# jtag_levelxlate.net
KiCad netlist of a schematic drawn in Altium Designer
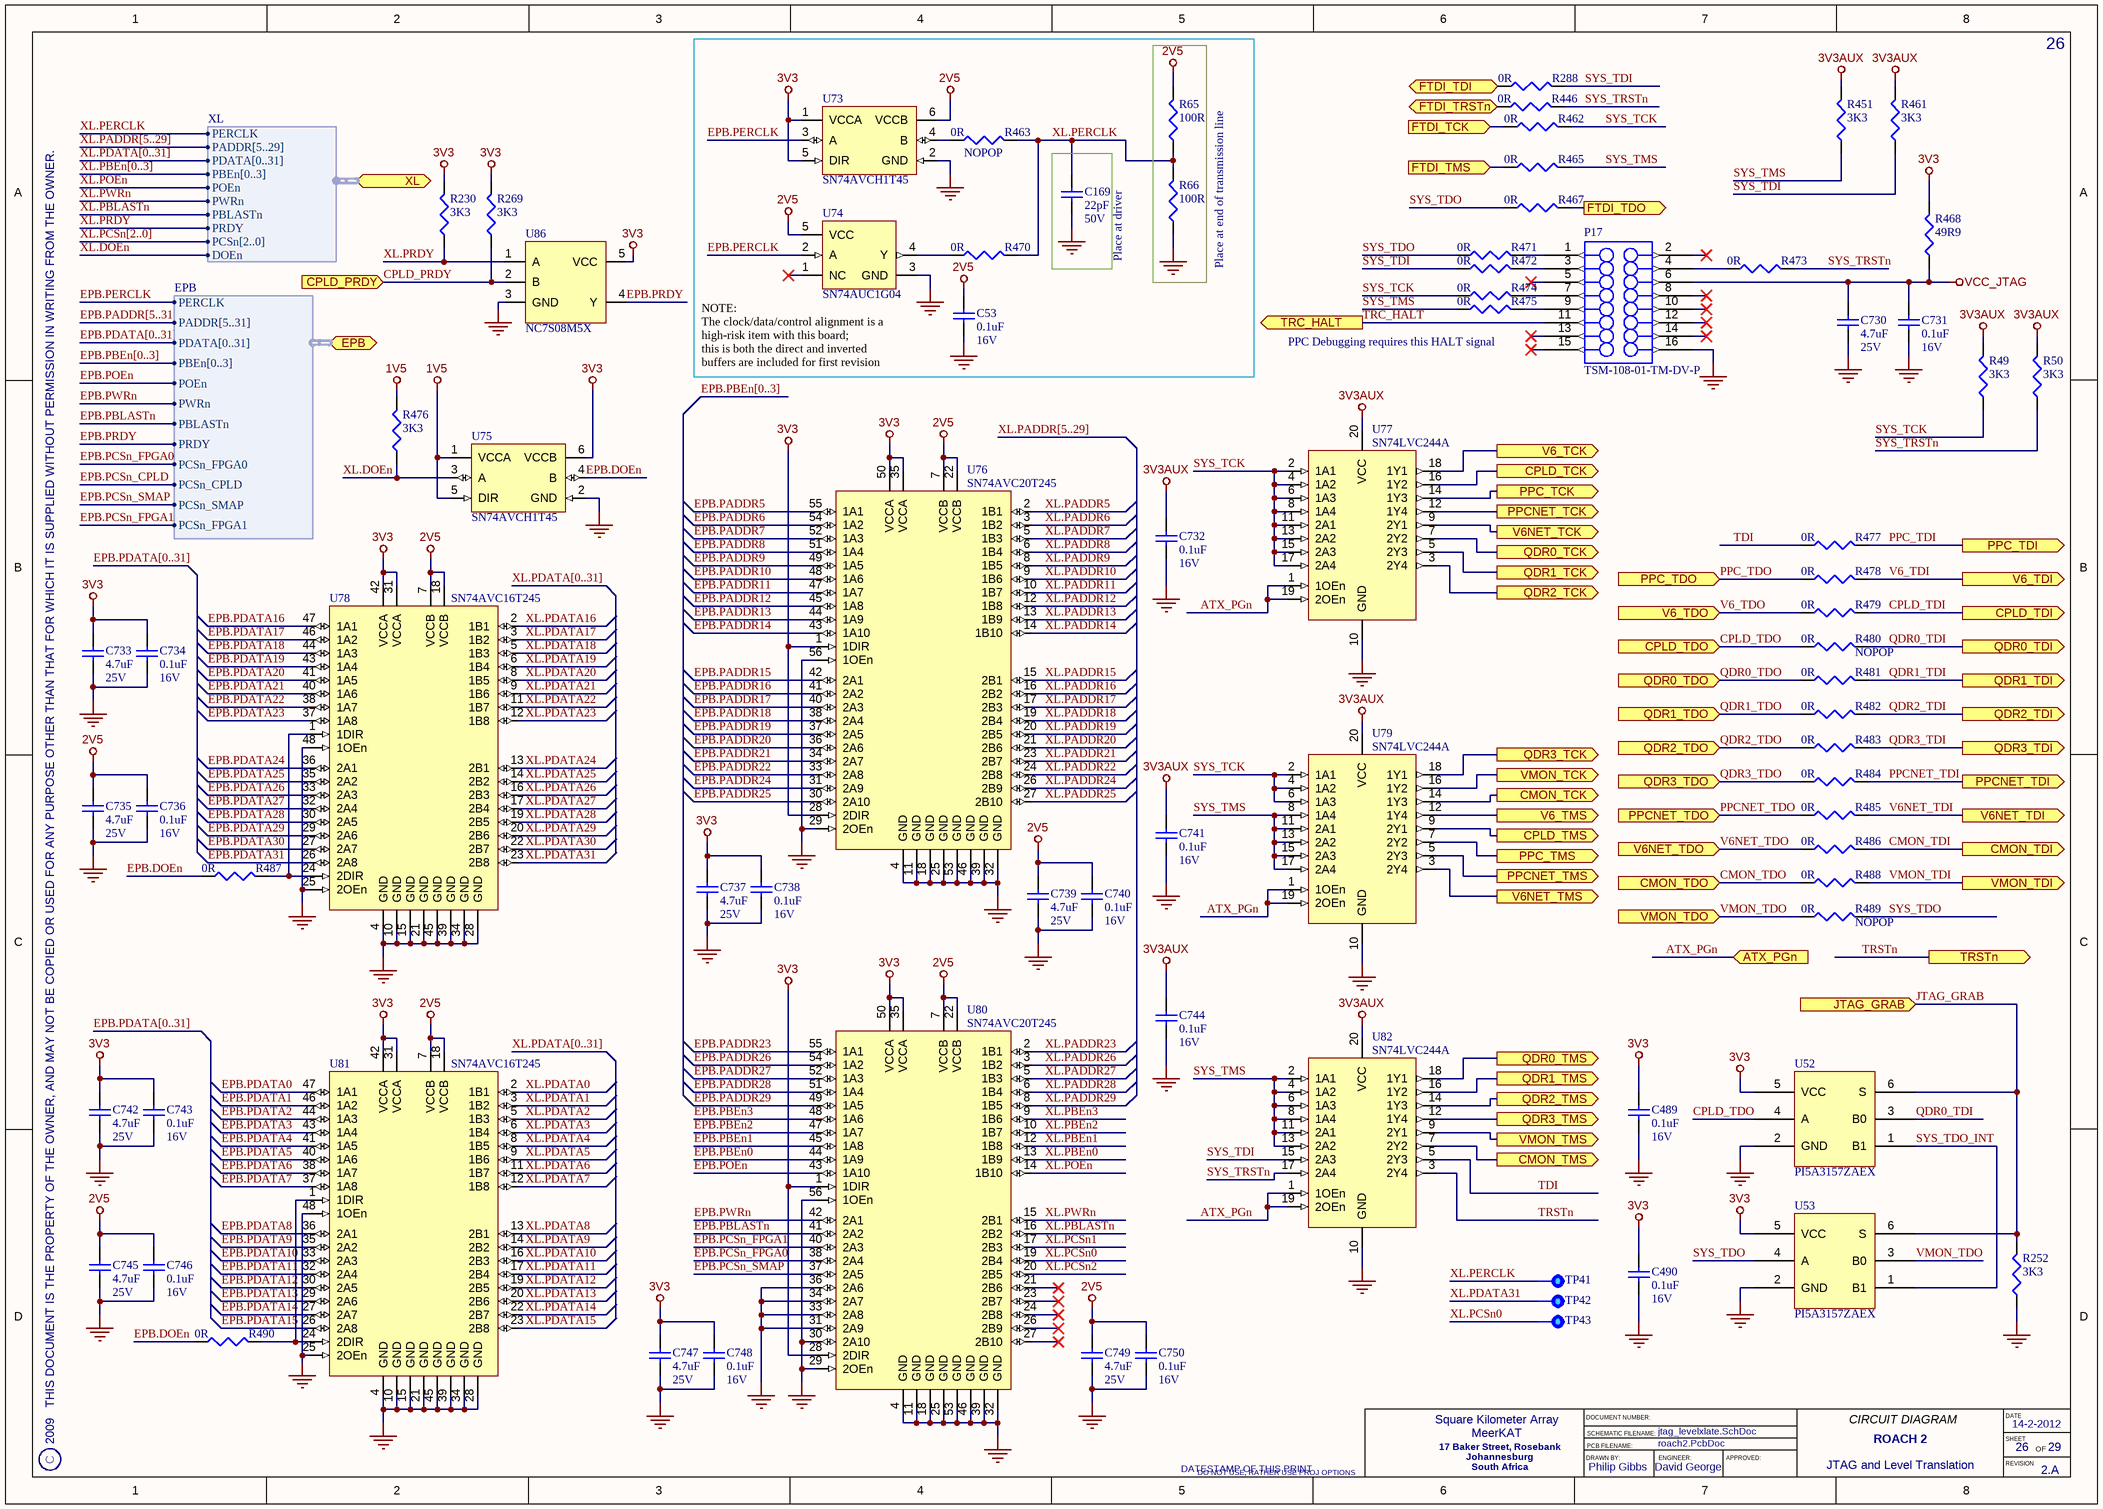
[diagram p0: jtag_levelxlate.SchDoc]

(export (version "E")
  (design (tool "Eeschema 10.0.6"))
  (components
    (comp (ref "C53")
      (value "0.1uF")
      (footprint "CAPC1005X60L")
      (description "0.1uF, Ceramic Capacitor")
      (fields
        (field (name "RATING") "16V")
        (field (name "MANUFACTURER") "VENKEL")
        (field (name "PARTNUM") "C0402X7R160-104KN")
      )
      (libsource (lib "altium_db") (part "CapStd"))
    )
    (comp (ref "C169")
      (value "22pF")
      (footprint "CAPC1005X55L")
      (description "22pF, Ceramic Capacitor")
      (fields
        (field (name "RATING") "50V")
        (field (name "MANUFACTURER") "MURATA")
        (field (name "PARTNUM") "GRM1555C1H220JZ01D")
      )
      (libsource (lib "altium_db") (part "CapStd"))
    )
    (comp (ref "C489")
      (value "0.1uF")
      (footprint "CAPC1005X60L")
      (description "0.1uF, Ceramic Capacitor")
      (fields
        (field (name "RATING") "16V")
        (field (name "MANUFACTURER") "VENKEL")
        (field (name "PARTNUM") "C0402X7R160-104KN")
      )
      (libsource (lib "altium_db") (part "CapStd"))
    )
    (comp (ref "C490")
      (value "0.1uF")
      (footprint "CAPC1005X60L")
      (description "0.1uF, Ceramic Capacitor")
      (fields
        (field (name "RATING") "16V")
        (field (name "MANUFACTURER") "VENKEL")
        (field (name "PARTNUM") "C0402X7R160-104KN")
      )
      (libsource (lib "altium_db") (part "CapStd"))
    )
    (comp (ref "C730")
      (value "4.7uF")
      (footprint "CAPC2012X127L")
      (description "4.7uF, Ceramic Capacitor")
      (fields
        (field (name "RATING") "25V")
        (field (name "MANUFACTURER") "MURATA")
        (field (name "PARTNUM") "GRM21BR61E475KA12K")
      )
      (libsource (lib "altium_db") (part "CapStd"))
    )
    (comp (ref "C731")
      (value "0.1uF")
      (footprint "CAPC1005X60L")
      (description "0.1uF, Ceramic Capacitor")
      (fields
        (field (name "RATING") "16V")
        (field (name "MANUFACTURER") "VENKEL")
        (field (name "PARTNUM") "C0402X7R160-104KN")
      )
      (libsource (lib "altium_db") (part "CapStd"))
    )
    (comp (ref "C732")
      (value "0.1uF")
      (footprint "CAPC1005X60L")
      (description "0.1uF, Ceramic Capacitor")
      (fields
        (field (name "RATING") "16V")
        (field (name "MANUFACTURER") "VENKEL")
        (field (name "PARTNUM") "C0402X7R160-104KN")
      )
      (libsource (lib "altium_db") (part "CapStd"))
    )
    (comp (ref "C733")
      (value "4.7uF")
      (footprint "CAPC2012X127L")
      (description "4.7uF, Ceramic Capacitor")
      (fields
        (field (name "RATING") "25V")
        (field (name "MANUFACTURER") "MURATA")
        (field (name "PARTNUM") "GRM21BR61E475KA12K")
      )
      (libsource (lib "altium_db") (part "CapStd"))
    )
    (comp (ref "C734")
      (value "0.1uF")
      (footprint "CAPC1005X60L")
      (description "0.1uF, Ceramic Capacitor")
      (fields
        (field (name "RATING") "16V")
        (field (name "MANUFACTURER") "VENKEL")
        (field (name "PARTNUM") "C0402X7R160-104KN")
      )
      (libsource (lib "altium_db") (part "CapStd"))
    )
    (comp (ref "C735")
      (value "4.7uF")
      (footprint "CAPC2012X127L")
      (description "4.7uF, Ceramic Capacitor")
      (fields
        (field (name "RATING") "25V")
        (field (name "MANUFACTURER") "MURATA")
        (field (name "PARTNUM") "GRM21BR61E475KA12K")
      )
      (libsource (lib "altium_db") (part "CapStd"))
    )
    (comp (ref "C736")
      (value "0.1uF")
      (footprint "CAPC1005X60L")
      (description "0.1uF, Ceramic Capacitor")
      (fields
        (field (name "RATING") "16V")
        (field (name "MANUFACTURER") "VENKEL")
        (field (name "PARTNUM") "C0402X7R160-104KN")
      )
      (libsource (lib "altium_db") (part "CapStd"))
    )
    (comp (ref "C737")
      (value "4.7uF")
      (footprint "CAPC2012X127L")
      (description "4.7uF, Ceramic Capacitor")
      (fields
        (field (name "RATING") "25V")
        (field (name "MANUFACTURER") "MURATA")
        (field (name "PARTNUM") "GRM21BR61E475KA12K")
      )
      (libsource (lib "altium_db") (part "CapStd"))
    )
    (comp (ref "C738")
      (value "0.1uF")
      (footprint "CAPC1005X60L")
      (description "0.1uF, Ceramic Capacitor")
      (fields
        (field (name "RATING") "16V")
        (field (name "MANUFACTURER") "VENKEL")
        (field (name "PARTNUM") "C0402X7R160-104KN")
      )
      (libsource (lib "altium_db") (part "CapStd"))
    )
    (comp (ref "C739")
      (value "4.7uF")
      (footprint "CAPC2012X127L")
      (description "4.7uF, Ceramic Capacitor")
      (fields
        (field (name "RATING") "25V")
        (field (name "MANUFACTURER") "MURATA")
        (field (name "PARTNUM") "GRM21BR61E475KA12K")
      )
      (libsource (lib "altium_db") (part "CapStd"))
    )
    (comp (ref "C740")
      (value "0.1uF")
      (footprint "CAPC1005X60L")
      (description "0.1uF, Ceramic Capacitor")
      (fields
        (field (name "RATING") "16V")
        (field (name "MANUFACTURER") "VENKEL")
        (field (name "PARTNUM") "C0402X7R160-104KN")
      )
      (libsource (lib "altium_db") (part "CapStd"))
    )
    (comp (ref "C741")
      (value "0.1uF")
      (footprint "CAPC1005X60L")
      (description "0.1uF, Ceramic Capacitor")
      (fields
        (field (name "RATING") "16V")
        (field (name "MANUFACTURER") "VENKEL")
        (field (name "PARTNUM") "C0402X7R160-104KN")
      )
      (libsource (lib "altium_db") (part "CapStd"))
    )
    (comp (ref "C742")
      (value "4.7uF")
      (footprint "CAPC2012X127L")
      (description "4.7uF, Ceramic Capacitor")
      (fields
        (field (name "RATING") "25V")
        (field (name "MANUFACTURER") "MURATA")
        (field (name "PARTNUM") "GRM21BR61E475KA12K")
      )
      (libsource (lib "altium_db") (part "CapStd"))
    )
    (comp (ref "C743")
      (value "0.1uF")
      (footprint "CAPC1005X60L")
      (description "0.1uF, Ceramic Capacitor")
      (fields
        (field (name "RATING") "16V")
        (field (name "MANUFACTURER") "VENKEL")
        (field (name "PARTNUM") "C0402X7R160-104KN")
      )
      (libsource (lib "altium_db") (part "CapStd"))
    )
    (comp (ref "C744")
      (value "0.1uF")
      (footprint "CAPC1005X60L")
      (description "0.1uF, Ceramic Capacitor")
      (fields
        (field (name "RATING") "16V")
        (field (name "MANUFACTURER") "VENKEL")
        (field (name "PARTNUM") "C0402X7R160-104KN")
      )
      (libsource (lib "altium_db") (part "CapStd"))
    )
    (comp (ref "C745")
      (value "4.7uF")
      (footprint "CAPC2012X127L")
      (description "4.7uF, Ceramic Capacitor")
      (fields
        (field (name "RATING") "25V")
        (field (name "MANUFACTURER") "MURATA")
        (field (name "PARTNUM") "GRM21BR61E475KA12K")
      )
      (libsource (lib "altium_db") (part "CapStd"))
    )
    (comp (ref "C746")
      (value "0.1uF")
      (footprint "CAPC1005X60L")
      (description "0.1uF, Ceramic Capacitor")
      (fields
        (field (name "RATING") "16V")
        (field (name "MANUFACTURER") "VENKEL")
        (field (name "PARTNUM") "C0402X7R160-104KN")
      )
      (libsource (lib "altium_db") (part "CapStd"))
    )
    (comp (ref "C747")
      (value "4.7uF")
      (footprint "CAPC2012X127L")
      (description "4.7uF, Ceramic Capacitor")
      (fields
        (field (name "RATING") "25V")
        (field (name "MANUFACTURER") "MURATA")
        (field (name "PARTNUM") "GRM21BR61E475KA12K")
      )
      (libsource (lib "altium_db") (part "CapStd"))
    )
    (comp (ref "C748")
      (value "0.1uF")
      (footprint "CAPC1005X60L")
      (description "0.1uF, Ceramic Capacitor")
      (fields
        (field (name "RATING") "16V")
        (field (name "MANUFACTURER") "VENKEL")
        (field (name "PARTNUM") "C0402X7R160-104KN")
      )
      (libsource (lib "altium_db") (part "CapStd"))
    )
    (comp (ref "C749")
      (value "4.7uF")
      (footprint "CAPC2012X127L")
      (description "4.7uF, Ceramic Capacitor")
      (fields
        (field (name "RATING") "25V")
        (field (name "MANUFACTURER") "MURATA")
        (field (name "PARTNUM") "GRM21BR61E475KA12K")
      )
      (libsource (lib "altium_db") (part "CapStd"))
    )
    (comp (ref "C750")
      (value "0.1uF")
      (footprint "CAPC1005X60L")
      (description "0.1uF, Ceramic Capacitor")
      (fields
        (field (name "RATING") "16V")
        (field (name "MANUFACTURER") "VENKEL")
        (field (name "PARTNUM") "C0402X7R160-104KN")
      )
      (libsource (lib "altium_db") (part "CapStd"))
    )
    (comp (ref "P17")
      (value "TSM-108-01-TM-DV-P")
      (footprint "SAMTEC_TSM-108-01-TM-DV-P")
      (description "2x8, 2.54 mm Pitch, Male Header")
      (fields (field (name "PARTNUM") "TSM-108-01-TM-DV-P") (field (name "MANUFACTURER") "SAMTEC"))
      (libsource (lib "altium_db") (part "con_hdr_2x8"))
    )
    (comp (ref "R49")
      (value "3K3")
      (footprint "RESC1005X40L")
      (description "3K3, 1.1mm x 0.5mm, Thick Film Resistor")
      (fields (field (name "MANUFACTURER") "ROYALOHM") (field (name "PARTNUM") "0402WGJ0332T1E"))
      (libsource (lib "altium_db") (part "ResStd"))
    )
    (comp (ref "R50")
      (value "3K3")
      (footprint "RESC1005X40L")
      (description "3K3, 1.1mm x 0.5mm, Thick Film Resistor")
      (fields (field (name "MANUFACTURER") "ROYALOHM") (field (name "PARTNUM") "0402WGJ0332T1E"))
      (libsource (lib "altium_db") (part "ResStd"))
    )
    (comp (ref "R65")
      (value "100R")
      (footprint "RESC1005X40L")
      (description "100R, 1.1mm x 0.5mm, Thick Film Resistor")
      (fields (field (name "MANUFACTURER") "ROYALOHM") (field (name "PARTNUM") "0402WGF0101T1E"))
      (libsource (lib "altium_db") (part "ResStd"))
    )
    (comp (ref "R66")
      (value "100R")
      (footprint "RESC1005X40L")
      (description "100R, 1.1mm x 0.5mm, Thick Film Resistor")
      (fields (field (name "MANUFACTURER") "ROYALOHM") (field (name "PARTNUM") "0402WGF0101T1E"))
      (libsource (lib "altium_db") (part "ResStd"))
    )
    (comp (ref "R230")
      (value "3K3")
      (footprint "RESC1005X40L")
      (description "3K3, 1.1mm x 0.5mm, Thick Film Resistor")
      (fields (field (name "MANUFACTURER") "ROYALOHM") (field (name "PARTNUM") "0402WGJ0332T1E"))
      (libsource (lib "altium_db") (part "ResStd"))
    )
    (comp (ref "R252")
      (value "3K3")
      (footprint "RESC1005X40L")
      (description "3K3, 1.1mm x 0.5mm, Thick Film Resistor")
      (fields (field (name "MANUFACTURER") "ROYALOHM") (field (name "PARTNUM") "0402WGJ0332T1E"))
      (libsource (lib "altium_db") (part "ResStd"))
    )
    (comp (ref "R269")
      (value "3K3")
      (footprint "RESC1005X40L")
      (description "3K3, 1.1mm x 0.5mm, Thick Film Resistor")
      (fields (field (name "MANUFACTURER") "ROYALOHM") (field (name "PARTNUM") "0402WGJ0332T1E"))
      (libsource (lib "altium_db") (part "ResStd"))
    )
    (comp (ref "R288")
      (value "0R")
      (footprint "RESC1005X40L")
      (description "0R, 1.1mm x 0.5mm, Thick Film Resistor")
      (fields (field (name "MANUFACTURER") "ROYALOHM") (field (name "PARTNUM") "0402WG00000T1E"))
      (libsource (lib "altium_db") (part "ResStd"))
    )
    (comp (ref "R446")
      (value "0R")
      (footprint "RESC1005X40L")
      (description "0R, 1.1mm x 0.5mm, Thick Film Resistor")
      (fields (field (name "MANUFACTURER") "ROYALOHM") (field (name "PARTNUM") "0402WG00000T1E"))
      (libsource (lib "altium_db") (part "ResStd"))
    )
    (comp (ref "R451")
      (value "3K3")
      (footprint "RESC1005X40L")
      (description "3K3, 1.1mm x 0.5mm, Thick Film Resistor")
      (fields (field (name "MANUFACTURER") "ROYALOHM") (field (name "PARTNUM") "0402WGJ0332T1E"))
      (libsource (lib "altium_db") (part "ResStd"))
    )
    (comp (ref "R461")
      (value "3K3")
      (footprint "RESC1005X40L")
      (description "3K3, 1.1mm x 0.5mm, Thick Film Resistor")
      (fields (field (name "MANUFACTURER") "ROYALOHM") (field (name "PARTNUM") "0402WGJ0332T1E"))
      (libsource (lib "altium_db") (part "ResStd"))
    )
    (comp (ref "R462")
      (value "0R")
      (footprint "RESC1005X40L")
      (description "0R, 1.1mm x 0.5mm, Thick Film Resistor")
      (fields (field (name "MANUFACTURER") "ROYALOHM") (field (name "PARTNUM") "0402WG00000T1E"))
      (libsource (lib "altium_db") (part "ResStd"))
    )
    (comp (ref "R463")
      (value "0R")
      (footprint "RESC1005X40L")
      (description "0R, 1.1mm x 0.5mm, Thick Film Resistor")
      (fields (field (name "MANUFACTURER") "ROYALOHM") (field (name "PARTNUM") "0402WG00000T1E"))
      (libsource (lib "altium_db") (part "ResStd"))
    )
    (comp (ref "R465")
      (value "0R")
      (footprint "RESC1005X40L")
      (description "0R, 1.1mm x 0.5mm, Thick Film Resistor")
      (fields (field (name "MANUFACTURER") "ROYALOHM") (field (name "PARTNUM") "0402WG00000T1E"))
      (libsource (lib "altium_db") (part "ResStd"))
    )
    (comp (ref "R467")
      (value "0R")
      (footprint "RESC1005X40L")
      (description "0R, 1.1mm x 0.5mm, Thick Film Resistor")
      (fields (field (name "MANUFACTURER") "ROYALOHM") (field (name "PARTNUM") "0402WG00000T1E"))
      (libsource (lib "altium_db") (part "ResStd"))
    )
    (comp (ref "R468")
      (value "49R9")
      (footprint "RESC1005X40L")
      (description "49R9, 1.1mm x 0.5mm, Thick Film Resistor")
      (fields (field (name "MANUFACTURER") "ROYALOHM") (field (name "PARTNUM") "0402WGF499JT1E"))
      (libsource (lib "altium_db") (part "ResStd"))
    )
    (comp (ref "R470")
      (value "0R")
      (footprint "RESC1005X40L")
      (description "0R, 1.1mm x 0.5mm, Thick Film Resistor")
      (fields (field (name "MANUFACTURER") "ROYALOHM") (field (name "PARTNUM") "0402WG00000T1E"))
      (libsource (lib "altium_db") (part "ResStd"))
    )
    (comp (ref "R471")
      (value "0R")
      (footprint "RESC1005X40L")
      (description "0R, 1.1mm x 0.5mm, Thick Film Resistor")
      (fields (field (name "MANUFACTURER") "ROYALOHM") (field (name "PARTNUM") "0402WG00000T1E"))
      (libsource (lib "altium_db") (part "ResStd"))
    )
    (comp (ref "R472")
      (value "0R")
      (footprint "RESC1005X40L")
      (description "0R, 1.1mm x 0.5mm, Thick Film Resistor")
      (fields (field (name "MANUFACTURER") "ROYALOHM") (field (name "PARTNUM") "0402WG00000T1E"))
      (libsource (lib "altium_db") (part "ResStd"))
    )
    (comp (ref "R473")
      (value "0R")
      (footprint "RESC1005X40L")
      (description "0R, 1.1mm x 0.5mm, Thick Film Resistor")
      (fields (field (name "MANUFACTURER") "ROYALOHM") (field (name "PARTNUM") "0402WG00000T1E"))
      (libsource (lib "altium_db") (part "ResStd"))
    )
    (comp (ref "R474")
      (value "0R")
      (footprint "RESC1005X40L")
      (description "0R, 1.1mm x 0.5mm, Thick Film Resistor")
      (fields (field (name "MANUFACTURER") "ROYALOHM") (field (name "PARTNUM") "0402WG00000T1E"))
      (libsource (lib "altium_db") (part "ResStd"))
    )
    (comp (ref "R475")
      (value "0R")
      (footprint "RESC1005X40L")
      (description "0R, 1.1mm x 0.5mm, Thick Film Resistor")
      (fields (field (name "MANUFACTURER") "ROYALOHM") (field (name "PARTNUM") "0402WG00000T1E"))
      (libsource (lib "altium_db") (part "ResStd"))
    )
    (comp (ref "R476")
      (value "3K3")
      (footprint "RESC1005X40L")
      (description "3K3, 1.1mm x 0.5mm, Thick Film Resistor")
      (fields (field (name "MANUFACTURER") "ROYALOHM") (field (name "PARTNUM") "0402WGJ0332T1E"))
      (libsource (lib "altium_db") (part "ResStd"))
    )
    (comp (ref "R477")
      (value "0R")
      (footprint "RESC1005X40L")
      (description "0R, 1.1mm x 0.5mm, Thick Film Resistor")
      (fields (field (name "MANUFACTURER") "ROYALOHM") (field (name "PARTNUM") "0402WG00000T1E"))
      (libsource (lib "altium_db") (part "ResStd"))
    )
    (comp (ref "R478")
      (value "0R")
      (footprint "RESC1005X40L")
      (description "0R, 1.1mm x 0.5mm, Thick Film Resistor")
      (fields (field (name "MANUFACTURER") "ROYALOHM") (field (name "PARTNUM") "0402WG00000T1E"))
      (libsource (lib "altium_db") (part "ResStd"))
    )
    (comp (ref "R479")
      (value "0R")
      (footprint "RESC1005X40L")
      (description "0R, 1.1mm x 0.5mm, Thick Film Resistor")
      (fields (field (name "MANUFACTURER") "ROYALOHM") (field (name "PARTNUM") "0402WG00000T1E"))
      (libsource (lib "altium_db") (part "ResStd"))
    )
    (comp (ref "R480")
      (value "0R")
      (footprint "RESC1005X40L")
      (description "0R, 1.1mm x 0.5mm, Thick Film Resistor")
      (fields (field (name "MANUFACTURER") "ROYALOHM") (field (name "PARTNUM") "0402WG00000T1E"))
      (libsource (lib "altium_db") (part "ResStd"))
    )
    (comp (ref "R481")
      (value "0R")
      (footprint "RESC1005X40L")
      (description "0R, 1.1mm x 0.5mm, Thick Film Resistor")
      (fields (field (name "MANUFACTURER") "ROYALOHM") (field (name "PARTNUM") "0402WG00000T1E"))
      (libsource (lib "altium_db") (part "ResStd"))
    )
    (comp (ref "R482")
      (value "0R")
      (footprint "RESC1005X40L")
      (description "0R, 1.1mm x 0.5mm, Thick Film Resistor")
      (fields (field (name "MANUFACTURER") "ROYALOHM") (field (name "PARTNUM") "0402WG00000T1E"))
      (libsource (lib "altium_db") (part "ResStd"))
    )
    (comp (ref "R483")
      (value "0R")
      (footprint "RESC1005X40L")
      (description "0R, 1.1mm x 0.5mm, Thick Film Resistor")
      (fields (field (name "MANUFACTURER") "ROYALOHM") (field (name "PARTNUM") "0402WG00000T1E"))
      (libsource (lib "altium_db") (part "ResStd"))
    )
    (comp (ref "R484")
      (value "0R")
      (footprint "RESC1005X40L")
      (description "0R, 1.1mm x 0.5mm, Thick Film Resistor")
      (fields (field (name "MANUFACTURER") "ROYALOHM") (field (name "PARTNUM") "0402WG00000T1E"))
      (libsource (lib "altium_db") (part "ResStd"))
    )
    (comp (ref "R485")
      (value "0R")
      (footprint "RESC1005X40L")
      (description "0R, 1.1mm x 0.5mm, Thick Film Resistor")
      (fields (field (name "MANUFACTURER") "ROYALOHM") (field (name "PARTNUM") "0402WG00000T1E"))
      (libsource (lib "altium_db") (part "ResStd"))
    )
    (comp (ref "R486")
      (value "0R")
      (footprint "RESC1005X40L")
      (description "0R, 1.1mm x 0.5mm, Thick Film Resistor")
      (fields (field (name "MANUFACTURER") "ROYALOHM") (field (name "PARTNUM") "0402WG00000T1E"))
      (libsource (lib "altium_db") (part "ResStd"))
    )
    (comp (ref "R487")
      (value "0R")
      (footprint "RESC1005X40L")
      (description "0R, 1.1mm x 0.5mm, Thick Film Resistor")
      (fields (field (name "MANUFACTURER") "ROYALOHM") (field (name "PARTNUM") "0402WG00000T1E"))
      (libsource (lib "altium_db") (part "ResStd"))
    )
    (comp (ref "R488")
      (value "0R")
      (footprint "RESC1005X40L")
      (description "0R, 1.1mm x 0.5mm, Thick Film Resistor")
      (fields (field (name "MANUFACTURER") "ROYALOHM") (field (name "PARTNUM") "0402WG00000T1E"))
      (libsource (lib "altium_db") (part "ResStd"))
    )
    (comp (ref "R489")
      (value "0R")
      (footprint "RESC1005X40L")
      (description "0R, 1.1mm x 0.5mm, Thick Film Resistor")
      (fields (field (name "MANUFACTURER") "ROYALOHM") (field (name "PARTNUM") "0402WG00000T1E"))
      (libsource (lib "altium_db") (part "ResStd"))
    )
    (comp (ref "R490")
      (value "0R")
      (footprint "RESC1005X40L")
      (description "0R, 1.1mm x 0.5mm, Thick Film Resistor")
      (fields (field (name "MANUFACTURER") "ROYALOHM") (field (name "PARTNUM") "0402WG00000T1E"))
      (libsource (lib "altium_db") (part "ResStd"))
    )
    (comp (ref "TP41")
      (value "Testpoint")
      (footprint "TP100")
      (description "1mm Diameter, through-hole, Circular Test-point")
      (libsource (lib "altium_db") (part "Testpoint"))
    )
    (comp (ref "TP42")
      (value "Testpoint")
      (footprint "TP100")
      (description "1mm Diameter, through-hole, Circular Test-point")
      (libsource (lib "altium_db") (part "Testpoint"))
    )
    (comp (ref "TP43")
      (value "Testpoint")
      (footprint "TP100")
      (description "1mm Diameter, through-hole, Circular Test-point")
      (libsource (lib "altium_db") (part "Testpoint"))
    )
    (comp (ref "U52")
      (value "PI5A3157ZAEX")
      (footprint "SC70-6")
      (description "Low voltage SPDT Analogue Switch")
      (fields (field (name "MANUFACTURER") "PERICOM"))
      (libsource (lib "altium_db") (part "PI5A3157ZAEX"))
    )
    (comp (ref "U53")
      (value "PI5A3157ZAEX")
      (footprint "SC70-6")
      (description "Low voltage SPDT Analogue Switch")
      (fields (field (name "MANUFACTURER") "PERICOM"))
      (libsource (lib "altium_db") (part "PI5A3157ZAEX"))
    )
    (comp (ref "U73")
      (value "SN74AVCH1T45")
      (footprint "SOT23-6")
      (description "Single-Bit Dual Supply Bus Transceiver with Configurable Voltage Translation and 3-State Outputs")
      (fields (field (name "MANUFACTURER") "Texas Instruments"))
      (libsource (lib "altium_db") (part "SN74AVCH1T45"))
    )
    (comp (ref "U74")
      (value "SN74AUC1G04")
      (footprint "SOT23-5")
      (description "Single Inverter Gate")
      (fields (field (name "MANUFACTURER") "Texas Instruments"))
      (libsource (lib "altium_db") (part "SN74AUC1G04"))
    )
    (comp (ref "U75")
      (value "SN74AVCH1T45")
      (footprint "SOT23-6")
      (description "Single-Bit Dual Supply Bus Transceiver with Configurable Voltage Translation and 3-State Outputs")
      (fields (field (name "MANUFACTURER") "Texas Instruments"))
      (libsource (lib "altium_db") (part "SN74AVCH1T45"))
    )
    (comp (ref "U76")
      (value "SN74AVC20T245")
      (footprint "PW056")
      (description "20-Bit Dual-Supply Bus Transceivers with Configurable Voltage Translation and 3-State Outputs")
      (fields (field (name "MANUFACTURER") "Texas Instruments"))
      (libsource (lib "altium_db") (part "SN74AVC20T245"))
    )
    (comp (ref "U77")
      (value "SN74LVC244A")
      (footprint "PW020")
      (description "Octal Buffer/Drive with 3-State Outputs")
      (fields (field (name "MANUFACTURER") "Texas Instruments"))
      (libsource (lib "altium_db") (part "SN74LVC244A"))
    )
    (comp (ref "U78")
      (value "SN74AVC16T245")
      (footprint "PW048")
      (description "16-BIT DUAL-SUPPLY BUS TRANSCEIVER WITH CONFIGURABLE VOLTAGE TRANSLATION AND 3-STATE OUTPUTS")
      (fields (field (name "MANUFACTURER") "Texas Instruments"))
      (libsource (lib "altium_db") (part "SN74AVC16T245"))
    )
    (comp (ref "U79")
      (value "SN74LVC244A")
      (footprint "PW020")
      (description "Octal Buffer/Drive with 3-State Outputs")
      (fields (field (name "MANUFACTURER") "Texas Instruments"))
      (libsource (lib "altium_db") (part "SN74LVC244A"))
    )
    (comp (ref "U80")
      (value "SN74AVC20T245")
      (footprint "PW056")
      (description "20-Bit Dual-Supply Bus Transceivers with Configurable Voltage Translation and 3-State Outputs")
      (fields (field (name "MANUFACTURER") "Texas Instruments"))
      (libsource (lib "altium_db") (part "SN74AVC20T245"))
    )
    (comp (ref "U81")
      (value "SN74AVC16T245")
      (footprint "PW048")
      (description "16-BIT DUAL-SUPPLY BUS TRANSCEIVER WITH CONFIGURABLE VOLTAGE TRANSLATION AND 3-STATE OUTPUTS")
      (fields (field (name "MANUFACTURER") "Texas Instruments"))
      (libsource (lib "altium_db") (part "SN74AVC16T245"))
    )
    (comp (ref "U82")
      (value "SN74LVC244A")
      (footprint "PW020")
      (description "Octal Buffer/Drive with 3-State Outputs")
      (fields (field (name "MANUFACTURER") "Texas Instruments"))
      (libsource (lib "altium_db") (part "SN74LVC244A"))
    )
    (comp (ref "U86")
      (value "NC7S08M5X")
      (footprint "SOT23-5")
      (description "TinyLogic® HS 2-Input AND Gate")
      (fields (field (name "MANUFACTURER") "Fairchild Semiconductor"))
      (libsource (lib "altium_db") (part "NC7S08"))
    )
  )
  (nets
    (net (code "5") (name "/ATX_PGn") (class "Default")
      (node (ref "U77") (pin "1") (pinfunction "1OEn_1") (pintype "input"))
      (node (ref "U77") (pin "19") (pinfunction "2OEn_19") (pintype "input"))
      (node (ref "U79") (pin "1") (pinfunction "1OEn_1") (pintype "input"))
      (node (ref "U79") (pin "19") (pinfunction "2OEn_19") (pintype "input"))
      (node (ref "U82") (pin "1") (pinfunction "1OEn_1") (pintype "input"))
      (node (ref "U82") (pin "19") (pinfunction "2OEn_19") (pintype "input"))
    )
    (net (code "6") (name "/CMON_TCK") (class "Default")
      (node (ref "U79") (pin "14") (pinfunction "1Y3_14") (pintype "output"))
    )
    (net (code "7") (name "/CMON_TDI") (class "Default")
      (node (ref "R486") (pin "2") (pinfunction "2_2") (pintype "passive"))
    )
    (net (code "8") (name "/CMON_TDO") (class "Default")
      (node (ref "R488") (pin "1") (pinfunction "1_1") (pintype "passive"))
    )
    (net (code "9") (name "/CMON_TMS") (class "Default")
      (node (ref "U82") (pin "7") (pinfunction "2Y2_7") (pintype "output"))
    )
    (net (code "10") (name "/CPLD_PRDY") (class "Default")
      (node (ref "R269") (pin "1") (pinfunction "1_1") (pintype "passive"))
      (node (ref "U86") (pin "2") (pinfunction "B_2") (pintype "passive"))
    )
    (net (code "11") (name "/CPLD_TCK") (class "Default")
      (node (ref "U77") (pin "16") (pinfunction "1Y2_16") (pintype "output"))
    )
    (net (code "12") (name "/CPLD_TDI") (class "Default")
      (node (ref "R479") (pin "2") (pinfunction "2_2") (pintype "passive"))
    )
    (net (code "13") (name "/CPLD_TDO") (class "Default")
      (node (ref "R480") (pin "1") (pinfunction "1_1") (pintype "passive"))
      (node (ref "U52") (pin "4") (pinfunction "A_4") (pintype "passive"))
    )
    (net (code "14") (name "/CPLD_TMS") (class "Default")
      (node (ref "U79") (pin "9") (pinfunction "2Y1_9") (pintype "output"))
    )
    (net (code "15") (name "/EPB.DOEn") (class "Default")
      (node (ref "R487") (pin "1") (pinfunction "1_1") (pintype "passive"))
      (node (ref "R490") (pin "1") (pinfunction "1_1") (pintype "passive"))
      (node (ref "U75") (pin "4") (pinfunction "B_4") (pintype "bidirectional"))
    )
    (net (code "16") (name "/EPB.PADDR5") (class "Default")
      (node (ref "U76") (pin "55") (pinfunction "1A1_55") (pintype "bidirectional"))
    )
    (net (code "17") (name "/EPB.PADDR6") (class "Default")
      (node (ref "U76") (pin "54") (pinfunction "1A2_54") (pintype "bidirectional"))
    )
    (net (code "18") (name "/EPB.PADDR7") (class "Default")
      (node (ref "U76") (pin "52") (pinfunction "1A3_52") (pintype "bidirectional"))
    )
    (net (code "19") (name "/EPB.PADDR8") (class "Default")
      (node (ref "U76") (pin "51") (pinfunction "1A4_51") (pintype "bidirectional"))
    )
    (net (code "20") (name "/EPB.PADDR9") (class "Default")
      (node (ref "U76") (pin "49") (pinfunction "1A5_49") (pintype "bidirectional"))
    )
    (net (code "21") (name "/EPB.PADDR10") (class "Default")
      (node (ref "U76") (pin "48") (pinfunction "1A6_48") (pintype "bidirectional"))
    )
    (net (code "22") (name "/EPB.PADDR11") (class "Default")
      (node (ref "U76") (pin "47") (pinfunction "1A7_47") (pintype "bidirectional"))
    )
    (net (code "23") (name "/EPB.PADDR12") (class "Default")
      (node (ref "U76") (pin "45") (pinfunction "1A8_45") (pintype "bidirectional"))
    )
    (net (code "24") (name "/EPB.PADDR13") (class "Default")
      (node (ref "U76") (pin "44") (pinfunction "1A9_44") (pintype "bidirectional"))
    )
    (net (code "25") (name "/EPB.PADDR14") (class "Default")
      (node (ref "U76") (pin "43") (pinfunction "1A10_43") (pintype "bidirectional"))
    )
    (net (code "26") (name "/EPB.PADDR15") (class "Default")
      (node (ref "U76") (pin "42") (pinfunction "2A1_42") (pintype "bidirectional"))
    )
    (net (code "27") (name "/EPB.PADDR16") (class "Default")
      (node (ref "U76") (pin "41") (pinfunction "2A2_41") (pintype "bidirectional"))
    )
    (net (code "28") (name "/EPB.PADDR17") (class "Default")
      (node (ref "U76") (pin "40") (pinfunction "2A3_40") (pintype "bidirectional"))
    )
    (net (code "29") (name "/EPB.PADDR18") (class "Default")
      (node (ref "U76") (pin "38") (pinfunction "2A4_38") (pintype "bidirectional"))
    )
    (net (code "30") (name "/EPB.PADDR19") (class "Default")
      (node (ref "U76") (pin "37") (pinfunction "2A5_37") (pintype "bidirectional"))
    )
    (net (code "31") (name "/EPB.PADDR20") (class "Default")
      (node (ref "U76") (pin "36") (pinfunction "2A6_36") (pintype "bidirectional"))
    )
    (net (code "32") (name "/EPB.PADDR21") (class "Default")
      (node (ref "U76") (pin "34") (pinfunction "2A7_34") (pintype "bidirectional"))
    )
    (net (code "33") (name "/EPB.PADDR22") (class "Default")
      (node (ref "U76") (pin "33") (pinfunction "2A8_33") (pintype "bidirectional"))
    )
    (net (code "34") (name "/EPB.PADDR23") (class "Default")
      (node (ref "U80") (pin "55") (pinfunction "1A1_55") (pintype "bidirectional"))
    )
    (net (code "35") (name "/EPB.PADDR24") (class "Default")
      (node (ref "U76") (pin "31") (pinfunction "2A9_31") (pintype "bidirectional"))
    )
    (net (code "36") (name "/EPB.PADDR25") (class "Default")
      (node (ref "U76") (pin "30") (pinfunction "2A10_30") (pintype "bidirectional"))
    )
    (net (code "37") (name "/EPB.PADDR26") (class "Default")
      (node (ref "U80") (pin "54") (pinfunction "1A2_54") (pintype "bidirectional"))
    )
    (net (code "38") (name "/EPB.PADDR27") (class "Default")
      (node (ref "U80") (pin "52") (pinfunction "1A3_52") (pintype "bidirectional"))
    )
    (net (code "39") (name "/EPB.PADDR28") (class "Default")
      (node (ref "U80") (pin "51") (pinfunction "1A4_51") (pintype "bidirectional"))
    )
    (net (code "40") (name "/EPB.PADDR29") (class "Default")
      (node (ref "U80") (pin "49") (pinfunction "1A5_49") (pintype "bidirectional"))
    )
    (net (code "42") (name "/EPB.PBEn0") (class "Default")
      (node (ref "U80") (pin "44") (pinfunction "1A9_44") (pintype "bidirectional"))
    )
    (net (code "43") (name "/EPB.PBEn1") (class "Default")
      (node (ref "U80") (pin "45") (pinfunction "1A8_45") (pintype "bidirectional"))
    )
    (net (code "44") (name "/EPB.PBEn2") (class "Default")
      (node (ref "U80") (pin "47") (pinfunction "1A7_47") (pintype "bidirectional"))
    )
    (net (code "45") (name "/EPB.PBEn3") (class "Default")
      (node (ref "U80") (pin "48") (pinfunction "1A6_48") (pintype "bidirectional"))
    )
    (net (code "47") (name "/EPB.PBLASTn") (class "Default")
      (node (ref "U80") (pin "41") (pinfunction "2A2_41") (pintype "bidirectional"))
    )
    (net (code "49") (name "/EPB.PCSn_FPGA0") (class "Default")
      (node (ref "U80") (pin "38") (pinfunction "2A4_38") (pintype "bidirectional"))
    )
    (net (code "50") (name "/EPB.PCSn_FPGA1") (class "Default")
      (node (ref "U80") (pin "40") (pinfunction "2A3_40") (pintype "bidirectional"))
    )
    (net (code "51") (name "/EPB.PCSn_SMAP") (class "Default")
      (node (ref "U80") (pin "37") (pinfunction "2A5_37") (pintype "bidirectional"))
    )
    (net (code "52") (name "/EPB.PDATA0") (class "Default")
      (node (ref "U81") (pin "47") (pinfunction "1A1_47") (pintype "bidirectional"))
    )
    (net (code "53") (name "/EPB.PDATA1") (class "Default")
      (node (ref "U81") (pin "46") (pinfunction "1A2_46") (pintype "bidirectional"))
    )
    (net (code "54") (name "/EPB.PDATA2") (class "Default")
      (node (ref "U81") (pin "44") (pinfunction "1A3_44") (pintype "bidirectional"))
    )
    (net (code "55") (name "/EPB.PDATA3") (class "Default")
      (node (ref "U81") (pin "43") (pinfunction "1A4_43") (pintype "bidirectional"))
    )
    (net (code "56") (name "/EPB.PDATA4") (class "Default")
      (node (ref "U81") (pin "41") (pinfunction "1A5_41") (pintype "bidirectional"))
    )
    (net (code "57") (name "/EPB.PDATA5") (class "Default")
      (node (ref "U81") (pin "40") (pinfunction "1A6_40") (pintype "bidirectional"))
    )
    (net (code "58") (name "/EPB.PDATA6") (class "Default")
      (node (ref "U81") (pin "38") (pinfunction "1A7_38") (pintype "bidirectional"))
    )
    (net (code "59") (name "/EPB.PDATA7") (class "Default")
      (node (ref "U81") (pin "37") (pinfunction "1A8_37") (pintype "bidirectional"))
    )
    (net (code "60") (name "/EPB.PDATA8") (class "Default")
      (node (ref "U81") (pin "36") (pinfunction "2A1_36") (pintype "bidirectional"))
    )
    (net (code "61") (name "/EPB.PDATA9") (class "Default")
      (node (ref "U81") (pin "35") (pinfunction "2A2_35") (pintype "bidirectional"))
    )
    (net (code "62") (name "/EPB.PDATA10") (class "Default")
      (node (ref "U81") (pin "33") (pinfunction "2A3_33") (pintype "bidirectional"))
    )
    (net (code "63") (name "/EPB.PDATA11") (class "Default")
      (node (ref "U81") (pin "32") (pinfunction "2A4_32") (pintype "bidirectional"))
    )
    (net (code "64") (name "/EPB.PDATA12") (class "Default")
      (node (ref "U81") (pin "30") (pinfunction "2A5_30") (pintype "bidirectional"))
    )
    (net (code "65") (name "/EPB.PDATA13") (class "Default")
      (node (ref "U81") (pin "29") (pinfunction "2A6_29") (pintype "bidirectional"))
    )
    (net (code "66") (name "/EPB.PDATA14") (class "Default")
      (node (ref "U81") (pin "27") (pinfunction "2A7_27") (pintype "bidirectional"))
    )
    (net (code "67") (name "/EPB.PDATA15") (class "Default")
      (node (ref "U81") (pin "26") (pinfunction "2A8_26") (pintype "bidirectional"))
    )
    (net (code "68") (name "/EPB.PDATA16") (class "Default")
      (node (ref "U78") (pin "47") (pinfunction "1A1_47") (pintype "bidirectional"))
    )
    (net (code "69") (name "/EPB.PDATA17") (class "Default")
      (node (ref "U78") (pin "46") (pinfunction "1A2_46") (pintype "bidirectional"))
    )
    (net (code "70") (name "/EPB.PDATA18") (class "Default")
      (node (ref "U78") (pin "44") (pinfunction "1A3_44") (pintype "bidirectional"))
    )
    (net (code "71") (name "/EPB.PDATA19") (class "Default")
      (node (ref "U78") (pin "43") (pinfunction "1A4_43") (pintype "bidirectional"))
    )
    (net (code "72") (name "/EPB.PDATA20") (class "Default")
      (node (ref "U78") (pin "41") (pinfunction "1A5_41") (pintype "bidirectional"))
    )
    (net (code "73") (name "/EPB.PDATA21") (class "Default")
      (node (ref "U78") (pin "40") (pinfunction "1A6_40") (pintype "bidirectional"))
    )
    (net (code "74") (name "/EPB.PDATA22") (class "Default")
      (node (ref "U78") (pin "38") (pinfunction "1A7_38") (pintype "bidirectional"))
    )
    (net (code "75") (name "/EPB.PDATA23") (class "Default")
      (node (ref "U78") (pin "37") (pinfunction "1A8_37") (pintype "bidirectional"))
    )
    (net (code "76") (name "/EPB.PDATA24") (class "Default")
      (node (ref "U78") (pin "36") (pinfunction "2A1_36") (pintype "bidirectional"))
    )
    (net (code "77") (name "/EPB.PDATA25") (class "Default")
      (node (ref "U78") (pin "35") (pinfunction "2A2_35") (pintype "bidirectional"))
    )
    (net (code "78") (name "/EPB.PDATA26") (class "Default")
      (node (ref "U78") (pin "33") (pinfunction "2A3_33") (pintype "bidirectional"))
    )
    (net (code "79") (name "/EPB.PDATA27") (class "Default")
      (node (ref "U78") (pin "32") (pinfunction "2A4_32") (pintype "bidirectional"))
    )
    (net (code "80") (name "/EPB.PDATA28") (class "Default")
      (node (ref "U78") (pin "30") (pinfunction "2A5_30") (pintype "bidirectional"))
    )
    (net (code "81") (name "/EPB.PDATA29") (class "Default")
      (node (ref "U78") (pin "29") (pinfunction "2A6_29") (pintype "bidirectional"))
    )
    (net (code "82") (name "/EPB.PDATA30") (class "Default")
      (node (ref "U78") (pin "27") (pinfunction "2A7_27") (pintype "bidirectional"))
    )
    (net (code "83") (name "/EPB.PDATA31") (class "Default")
      (node (ref "U78") (pin "26") (pinfunction "2A8_26") (pintype "bidirectional"))
    )
    (net (code "85") (name "/EPB.PERCLK") (class "Default")
      (node (ref "U73") (pin "3") (pinfunction "A_3") (pintype "bidirectional"))
      (node (ref "U74") (pin "2") (pinfunction "A_2") (pintype "input"))
    )
    (net (code "86") (name "/EPB.POEn") (class "Default")
      (node (ref "U80") (pin "43") (pinfunction "1A10_43") (pintype "bidirectional"))
    )
    (net (code "87") (name "/EPB.PRDY") (class "Default")
      (node (ref "U86") (pin "4") (pinfunction "Y_4") (pintype "passive"))
    )
    (net (code "88") (name "/EPB.PWRn") (class "Default")
      (node (ref "U80") (pin "42") (pinfunction "2A1_42") (pintype "bidirectional"))
    )
    (net (code "89") (name "/FTDI_TCK") (class "Default")
      (node (ref "R462") (pin "1") (pinfunction "1_1") (pintype "passive"))
    )
    (net (code "90") (name "/FTDI_TDI") (class "Default")
      (node (ref "R288") (pin "1") (pinfunction "1_1") (pintype "passive"))
    )
    (net (code "91") (name "/FTDI_TDO") (class "Default")
      (node (ref "R467") (pin "2") (pinfunction "2_2") (pintype "passive"))
    )
    (net (code "92") (name "/FTDI_TMS") (class "Default")
      (node (ref "R465") (pin "1") (pinfunction "1_1") (pintype "passive"))
    )
    (net (code "93") (name "/FTDI_TRSTn") (class "Default")
      (node (ref "R446") (pin "1") (pinfunction "1_1") (pintype "passive"))
    )
    (net (code "94") (name "/JTAG_GRAB") (class "Default")
      (node (ref "R252") (pin "2") (pinfunction "2_2") (pintype "passive"))
      (node (ref "U52") (pin "6") (pinfunction "S_6") (pintype "passive"))
      (node (ref "U53") (pin "6") (pinfunction "S_6") (pintype "passive"))
    )
    (net (code "95") (name "/PPCNET_TCK") (class "Default")
      (node (ref "U77") (pin "12") (pinfunction "1Y4_12") (pintype "output"))
    )
    (net (code "96") (name "/PPCNET_TDI") (class "Default")
      (node (ref "R484") (pin "2") (pinfunction "2_2") (pintype "passive"))
    )
    (net (code "97") (name "/PPCNET_TDO") (class "Default")
      (node (ref "R485") (pin "1") (pinfunction "1_1") (pintype "passive"))
    )
    (net (code "98") (name "/PPCNET_TMS") (class "Default")
      (node (ref "U79") (pin "5") (pinfunction "2Y3_5") (pintype "output"))
    )
    (net (code "99") (name "/PPC_TCK") (class "Default")
      (node (ref "U77") (pin "14") (pinfunction "1Y3_14") (pintype "output"))
    )
    (net (code "100") (name "/PPC_TDI") (class "Default")
      (node (ref "R477") (pin "2") (pinfunction "2_2") (pintype "passive"))
    )
    (net (code "101") (name "/PPC_TDO") (class "Default")
      (node (ref "R478") (pin "1") (pinfunction "1_1") (pintype "passive"))
    )
    (net (code "102") (name "/PPC_TMS") (class "Default")
      (node (ref "U79") (pin "7") (pinfunction "2Y2_7") (pintype "output"))
    )
    (net (code "103") (name "/QDR0_TCK") (class "Default")
      (node (ref "U77") (pin "7") (pinfunction "2Y2_7") (pintype "output"))
    )
    (net (code "104") (name "/QDR0_TDI") (class "Default")
      (node (ref "R480") (pin "2") (pinfunction "2_2") (pintype "passive"))
      (node (ref "U52") (pin "3") (pinfunction "B0_3") (pintype "passive"))
    )
    (net (code "105") (name "/QDR0_TDO") (class "Default")
      (node (ref "R481") (pin "1") (pinfunction "1_1") (pintype "passive"))
    )
    (net (code "106") (name "/QDR0_TMS") (class "Default")
      (node (ref "U82") (pin "18") (pinfunction "1Y1_18") (pintype "output"))
    )
    (net (code "107") (name "/QDR1_TCK") (class "Default")
      (node (ref "U77") (pin "5") (pinfunction "2Y3_5") (pintype "output"))
    )
    (net (code "108") (name "/QDR1_TDI") (class "Default")
      (node (ref "R481") (pin "2") (pinfunction "2_2") (pintype "passive"))
    )
    (net (code "109") (name "/QDR1_TDO") (class "Default")
      (node (ref "R482") (pin "1") (pinfunction "1_1") (pintype "passive"))
    )
    (net (code "110") (name "/QDR1_TMS") (class "Default")
      (node (ref "U82") (pin "16") (pinfunction "1Y2_16") (pintype "output"))
    )
    (net (code "111") (name "/QDR2_TCK") (class "Default")
      (node (ref "U77") (pin "3") (pinfunction "2Y4_3") (pintype "output"))
    )
    (net (code "112") (name "/QDR2_TDI") (class "Default")
      (node (ref "R482") (pin "2") (pinfunction "2_2") (pintype "passive"))
    )
    (net (code "113") (name "/QDR2_TDO") (class "Default")
      (node (ref "R483") (pin "1") (pinfunction "1_1") (pintype "passive"))
    )
    (net (code "114") (name "/QDR2_TMS") (class "Default")
      (node (ref "U82") (pin "14") (pinfunction "1Y3_14") (pintype "output"))
    )
    (net (code "115") (name "/QDR3_TCK") (class "Default")
      (node (ref "U79") (pin "18") (pinfunction "1Y1_18") (pintype "output"))
    )
    (net (code "116") (name "/QDR3_TDI") (class "Default")
      (node (ref "R483") (pin "2") (pinfunction "2_2") (pintype "passive"))
    )
    (net (code "117") (name "/QDR3_TDO") (class "Default")
      (node (ref "R484") (pin "1") (pinfunction "1_1") (pintype "passive"))
    )
    (net (code "118") (name "/QDR3_TMS") (class "Default")
      (node (ref "U82") (pin "12") (pinfunction "1Y4_12") (pintype "output"))
    )
    (net (code "119") (name "/SYS_TCK") (class "Default")
      (node (ref "R462") (pin "2") (pinfunction "2_2") (pintype "passive"))
      (node (ref "R474") (pin "1") (pinfunction "1_1") (pintype "passive"))
      (node (ref "R49") (pin "1") (pinfunction "1_1") (pintype "passive"))
      (node (ref "U77") (pin "11") (pinfunction "2A1_11") (pintype "input"))
      (node (ref "U77") (pin "13") (pinfunction "2A2_13") (pintype "input"))
      (node (ref "U77") (pin "15") (pinfunction "2A3_15") (pintype "input"))
      (node (ref "U77") (pin "17") (pinfunction "2A4_17") (pintype "input"))
      (node (ref "U77") (pin "2") (pinfunction "1A1_2") (pintype "input"))
      (node (ref "U77") (pin "4") (pinfunction "1A2_4") (pintype "input"))
      (node (ref "U77") (pin "6") (pinfunction "1A3_6") (pintype "input"))
      (node (ref "U77") (pin "8") (pinfunction "1A4_8") (pintype "input"))
      (node (ref "U79") (pin "2") (pinfunction "1A1_2") (pintype "input"))
      (node (ref "U79") (pin "4") (pinfunction "1A2_4") (pintype "input"))
      (node (ref "U79") (pin "6") (pinfunction "1A3_6") (pintype "input"))
    )
    (net (code "120") (name "/SYS_TDI") (class "Default")
      (node (ref "R288") (pin "2") (pinfunction "2_2") (pintype "passive"))
      (node (ref "R461") (pin "1") (pinfunction "1_1") (pintype "passive"))
      (node (ref "R472") (pin "1") (pinfunction "1_1") (pintype "passive"))
      (node (ref "U82") (pin "15") (pinfunction "2A3_15") (pintype "input"))
    )
    (net (code "121") (name "/SYS_TDO") (class "Default")
      (node (ref "R467") (pin "1") (pinfunction "1_1") (pintype "passive"))
      (node (ref "R471") (pin "1") (pinfunction "1_1") (pintype "passive"))
      (node (ref "R489") (pin "2") (pinfunction "2_2") (pintype "passive"))
      (node (ref "U53") (pin "4") (pinfunction "A_4") (pintype "passive"))
    )
    (net (code "122") (name "/SYS_TDO_INT") (class "Default")
      (node (ref "U52") (pin "1") (pinfunction "B1_1") (pintype "passive"))
      (node (ref "U53") (pin "1") (pinfunction "B1_1") (pintype "passive"))
    )
    (net (code "123") (name "/SYS_TMS") (class "Default")
      (node (ref "R451") (pin "1") (pinfunction "1_1") (pintype "passive"))
      (node (ref "R465") (pin "2") (pinfunction "2_2") (pintype "passive"))
      (node (ref "R475") (pin "1") (pinfunction "1_1") (pintype "passive"))
      (node (ref "U79") (pin "11") (pinfunction "2A1_11") (pintype "input"))
      (node (ref "U79") (pin "13") (pinfunction "2A2_13") (pintype "input"))
      (node (ref "U79") (pin "15") (pinfunction "2A3_15") (pintype "input"))
      (node (ref "U79") (pin "17") (pinfunction "2A4_17") (pintype "input"))
      (node (ref "U79") (pin "8") (pinfunction "1A4_8") (pintype "input"))
      (node (ref "U82") (pin "11") (pinfunction "2A1_11") (pintype "input"))
      (node (ref "U82") (pin "13") (pinfunction "2A2_13") (pintype "input"))
      (node (ref "U82") (pin "2") (pinfunction "1A1_2") (pintype "input"))
      (node (ref "U82") (pin "4") (pinfunction "1A2_4") (pintype "input"))
      (node (ref "U82") (pin "6") (pinfunction "1A3_6") (pintype "input"))
      (node (ref "U82") (pin "8") (pinfunction "1A4_8") (pintype "input"))
    )
    (net (code "124") (name "/SYS_TRSTn") (class "Default")
      (node (ref "R446") (pin "2") (pinfunction "2_2") (pintype "passive"))
      (node (ref "R473") (pin "2") (pinfunction "2_2") (pintype "passive"))
      (node (ref "R50") (pin "1") (pinfunction "1_1") (pintype "passive"))
      (node (ref "U82") (pin "17") (pinfunction "2A4_17") (pintype "input"))
    )
    (net (code "125") (name "/TDI") (class "Default")
      (node (ref "R477") (pin "1") (pinfunction "1_1") (pintype "passive"))
      (node (ref "U82") (pin "5") (pinfunction "2Y3_5") (pintype "output"))
    )
    (net (code "126") (name "/TRC_HALT") (class "Default")
      (node (ref "P17") (pin "11") (pinfunction "A11_11") (pintype "output"))
    )
    (net (code "127") (name "/TRSTn") (class "Default")
      (node (ref "U82") (pin "3") (pinfunction "2Y4_3") (pintype "output"))
    )
    (net (code "128") (name "/V6NET_TCK") (class "Default")
      (node (ref "U77") (pin "9") (pinfunction "2Y1_9") (pintype "output"))
    )
    (net (code "129") (name "/V6NET_TDI") (class "Default")
      (node (ref "R485") (pin "2") (pinfunction "2_2") (pintype "passive"))
    )
    (net (code "130") (name "/V6NET_TDO") (class "Default")
      (node (ref "R486") (pin "1") (pinfunction "1_1") (pintype "passive"))
    )
    (net (code "131") (name "/V6NET_TMS") (class "Default")
      (node (ref "U79") (pin "3") (pinfunction "2Y4_3") (pintype "output"))
    )
    (net (code "132") (name "/V6_TCK") (class "Default")
      (node (ref "U77") (pin "18") (pinfunction "1Y1_18") (pintype "output"))
    )
    (net (code "133") (name "/V6_TDI") (class "Default")
      (node (ref "R478") (pin "2") (pinfunction "2_2") (pintype "passive"))
    )
    (net (code "134") (name "/V6_TDO") (class "Default")
      (node (ref "R479") (pin "1") (pinfunction "1_1") (pintype "passive"))
    )
    (net (code "135") (name "/V6_TMS") (class "Default")
      (node (ref "U79") (pin "12") (pinfunction "1Y4_12") (pintype "output"))
    )
    (net (code "136") (name "/VMON_TCK") (class "Default")
      (node (ref "U79") (pin "16") (pinfunction "1Y2_16") (pintype "output"))
    )
    (net (code "137") (name "/VMON_TDI") (class "Default")
      (node (ref "R488") (pin "2") (pinfunction "2_2") (pintype "passive"))
    )
    (net (code "138") (name "/VMON_TDO") (class "Default")
      (node (ref "R489") (pin "1") (pinfunction "1_1") (pintype "passive"))
      (node (ref "U53") (pin "3") (pinfunction "B0_3") (pintype "passive"))
    )
    (net (code "139") (name "/VMON_TMS") (class "Default")
      (node (ref "U82") (pin "9") (pinfunction "2Y1_9") (pintype "output"))
    )
    (net (code "140") (name "/XL.DOEn") (class "Default")
      (node (ref "R476") (pin "1") (pinfunction "1_1") (pintype "passive"))
      (node (ref "U75") (pin "3") (pinfunction "A_3") (pintype "bidirectional"))
    )
    (net (code "141") (name "/XL.PADDR5") (class "Default")
      (node (ref "U76") (pin "2") (pinfunction "1B1_2") (pintype "bidirectional"))
    )
    (net (code "142") (name "/XL.PADDR6") (class "Default")
      (node (ref "U76") (pin "3") (pinfunction "1B2_3") (pintype "bidirectional"))
    )
    (net (code "143") (name "/XL.PADDR7") (class "Default")
      (node (ref "U76") (pin "5") (pinfunction "1B3_5") (pintype "bidirectional"))
    )
    (net (code "144") (name "/XL.PADDR8") (class "Default")
      (node (ref "U76") (pin "6") (pinfunction "1B4_6") (pintype "bidirectional"))
    )
    (net (code "145") (name "/XL.PADDR9") (class "Default")
      (node (ref "U76") (pin "8") (pinfunction "1B5_8") (pintype "bidirectional"))
    )
    (net (code "146") (name "/XL.PADDR10") (class "Default")
      (node (ref "U76") (pin "9") (pinfunction "1B6_9") (pintype "bidirectional"))
    )
    (net (code "147") (name "/XL.PADDR11") (class "Default")
      (node (ref "U76") (pin "10") (pinfunction "1B7_10") (pintype "bidirectional"))
    )
    (net (code "148") (name "/XL.PADDR12") (class "Default")
      (node (ref "U76") (pin "12") (pinfunction "1B8_12") (pintype "bidirectional"))
    )
    (net (code "149") (name "/XL.PADDR13") (class "Default")
      (node (ref "U76") (pin "13") (pinfunction "1B9_13") (pintype "bidirectional"))
    )
    (net (code "150") (name "/XL.PADDR14") (class "Default")
      (node (ref "U76") (pin "14") (pinfunction "1B10_14") (pintype "bidirectional"))
    )
    (net (code "151") (name "/XL.PADDR15") (class "Default")
      (node (ref "U76") (pin "15") (pinfunction "2B1_15") (pintype "bidirectional"))
    )
    (net (code "152") (name "/XL.PADDR16") (class "Default")
      (node (ref "U76") (pin "16") (pinfunction "2B2_16") (pintype "bidirectional"))
    )
    (net (code "153") (name "/XL.PADDR17") (class "Default")
      (node (ref "U76") (pin "17") (pinfunction "2B3_17") (pintype "bidirectional"))
    )
    (net (code "154") (name "/XL.PADDR18") (class "Default")
      (node (ref "U76") (pin "19") (pinfunction "2B4_19") (pintype "bidirectional"))
    )
    (net (code "155") (name "/XL.PADDR19") (class "Default")
      (node (ref "U76") (pin "20") (pinfunction "2B5_20") (pintype "bidirectional"))
    )
    (net (code "156") (name "/XL.PADDR20") (class "Default")
      (node (ref "U76") (pin "21") (pinfunction "2B6_21") (pintype "bidirectional"))
    )
    (net (code "157") (name "/XL.PADDR21") (class "Default")
      (node (ref "U76") (pin "23") (pinfunction "2B7_23") (pintype "bidirectional"))
    )
    (net (code "158") (name "/XL.PADDR22") (class "Default")
      (node (ref "U76") (pin "24") (pinfunction "2B8_24") (pintype "bidirectional"))
    )
    (net (code "159") (name "/XL.PADDR23") (class "Default")
      (node (ref "U80") (pin "2") (pinfunction "1B1_2") (pintype "bidirectional"))
    )
    (net (code "160") (name "/XL.PADDR24") (class "Default")
      (node (ref "U76") (pin "26") (pinfunction "2B9_26") (pintype "bidirectional"))
    )
    (net (code "161") (name "/XL.PADDR25") (class "Default")
      (node (ref "U76") (pin "27") (pinfunction "2B10_27") (pintype "bidirectional"))
    )
    (net (code "162") (name "/XL.PADDR26") (class "Default")
      (node (ref "U80") (pin "3") (pinfunction "1B2_3") (pintype "bidirectional"))
    )
    (net (code "163") (name "/XL.PADDR27") (class "Default")
      (node (ref "U80") (pin "5") (pinfunction "1B3_5") (pintype "bidirectional"))
    )
    (net (code "164") (name "/XL.PADDR28") (class "Default")
      (node (ref "U80") (pin "6") (pinfunction "1B4_6") (pintype "bidirectional"))
    )
    (net (code "165") (name "/XL.PADDR29") (class "Default")
      (node (ref "U80") (pin "8") (pinfunction "1B5_8") (pintype "bidirectional"))
    )
    (net (code "167") (name "/XL.PBEn0") (class "Default")
      (node (ref "U80") (pin "13") (pinfunction "1B9_13") (pintype "bidirectional"))
    )
    (net (code "168") (name "/XL.PBEn1") (class "Default")
      (node (ref "U80") (pin "12") (pinfunction "1B8_12") (pintype "bidirectional"))
    )
    (net (code "169") (name "/XL.PBEn2") (class "Default")
      (node (ref "U80") (pin "10") (pinfunction "1B7_10") (pintype "bidirectional"))
    )
    (net (code "170") (name "/XL.PBEn3") (class "Default")
      (node (ref "U80") (pin "9") (pinfunction "1B6_9") (pintype "bidirectional"))
    )
    (net (code "172") (name "/XL.PBLASTn") (class "Default")
      (node (ref "U80") (pin "16") (pinfunction "2B2_16") (pintype "bidirectional"))
    )
    (net (code "173") (name "/XL.PCSn0") (class "Default")
      (node (ref "TP43") (pin "1") (pinfunction "1_1") (pintype "passive"))
      (node (ref "U80") (pin "19") (pinfunction "2B4_19") (pintype "bidirectional"))
    )
    (net (code "174") (name "/XL.PCSn1") (class "Default")
      (node (ref "U80") (pin "17") (pinfunction "2B3_17") (pintype "bidirectional"))
    )
    (net (code "175") (name "/XL.PCSn2") (class "Default")
      (node (ref "U80") (pin "20") (pinfunction "2B5_20") (pintype "bidirectional"))
    )
    (net (code "177") (name "/XL.PDATA0") (class "Default")
      (node (ref "U81") (pin "2") (pinfunction "1B1_2") (pintype "bidirectional"))
    )
    (net (code "178") (name "/XL.PDATA1") (class "Default")
      (node (ref "U81") (pin "3") (pinfunction "1B2_3") (pintype "bidirectional"))
    )
    (net (code "179") (name "/XL.PDATA2") (class "Default")
      (node (ref "U81") (pin "5") (pinfunction "1B3_5") (pintype "bidirectional"))
    )
    (net (code "180") (name "/XL.PDATA3") (class "Default")
      (node (ref "U81") (pin "6") (pinfunction "1B4_6") (pintype "bidirectional"))
    )
    (net (code "181") (name "/XL.PDATA4") (class "Default")
      (node (ref "U81") (pin "8") (pinfunction "1B5_8") (pintype "bidirectional"))
    )
    (net (code "182") (name "/XL.PDATA5") (class "Default")
      (node (ref "U81") (pin "9") (pinfunction "1B6_9") (pintype "bidirectional"))
    )
    (net (code "183") (name "/XL.PDATA6") (class "Default")
      (node (ref "U81") (pin "11") (pinfunction "1B7_11") (pintype "bidirectional"))
    )
    (net (code "184") (name "/XL.PDATA7") (class "Default")
      (node (ref "U81") (pin "12") (pinfunction "1B8_12") (pintype "bidirectional"))
    )
    (net (code "185") (name "/XL.PDATA8") (class "Default")
      (node (ref "U81") (pin "13") (pinfunction "2B1_13") (pintype "bidirectional"))
    )
    (net (code "186") (name "/XL.PDATA9") (class "Default")
      (node (ref "U81") (pin "14") (pinfunction "2B2_14") (pintype "bidirectional"))
    )
    (net (code "187") (name "/XL.PDATA10") (class "Default")
      (node (ref "U81") (pin "16") (pinfunction "2B3_16") (pintype "bidirectional"))
    )
    (net (code "188") (name "/XL.PDATA11") (class "Default")
      (node (ref "U81") (pin "17") (pinfunction "2B4_17") (pintype "bidirectional"))
    )
    (net (code "189") (name "/XL.PDATA12") (class "Default")
      (node (ref "U81") (pin "19") (pinfunction "2B5_19") (pintype "bidirectional"))
    )
    (net (code "190") (name "/XL.PDATA13") (class "Default")
      (node (ref "U81") (pin "20") (pinfunction "2B6_20") (pintype "bidirectional"))
    )
    (net (code "191") (name "/XL.PDATA14") (class "Default")
      (node (ref "U81") (pin "22") (pinfunction "2B7_22") (pintype "bidirectional"))
    )
    (net (code "192") (name "/XL.PDATA15") (class "Default")
      (node (ref "U81") (pin "23") (pinfunction "2B8_23") (pintype "bidirectional"))
    )
    (net (code "193") (name "/XL.PDATA16") (class "Default")
      (node (ref "U78") (pin "2") (pinfunction "1B1_2") (pintype "bidirectional"))
    )
    (net (code "194") (name "/XL.PDATA17") (class "Default")
      (node (ref "U78") (pin "3") (pinfunction "1B2_3") (pintype "bidirectional"))
    )
    (net (code "195") (name "/XL.PDATA18") (class "Default")
      (node (ref "U78") (pin "5") (pinfunction "1B3_5") (pintype "bidirectional"))
    )
    (net (code "196") (name "/XL.PDATA19") (class "Default")
      (node (ref "U78") (pin "6") (pinfunction "1B4_6") (pintype "bidirectional"))
    )
    (net (code "197") (name "/XL.PDATA20") (class "Default")
      (node (ref "U78") (pin "8") (pinfunction "1B5_8") (pintype "bidirectional"))
    )
    (net (code "198") (name "/XL.PDATA21") (class "Default")
      (node (ref "U78") (pin "9") (pinfunction "1B6_9") (pintype "bidirectional"))
    )
    (net (code "199") (name "/XL.PDATA22") (class "Default")
      (node (ref "U78") (pin "11") (pinfunction "1B7_11") (pintype "bidirectional"))
    )
    (net (code "200") (name "/XL.PDATA23") (class "Default")
      (node (ref "U78") (pin "12") (pinfunction "1B8_12") (pintype "bidirectional"))
    )
    (net (code "201") (name "/XL.PDATA24") (class "Default")
      (node (ref "U78") (pin "13") (pinfunction "2B1_13") (pintype "bidirectional"))
    )
    (net (code "202") (name "/XL.PDATA25") (class "Default")
      (node (ref "U78") (pin "14") (pinfunction "2B2_14") (pintype "bidirectional"))
    )
    (net (code "203") (name "/XL.PDATA26") (class "Default")
      (node (ref "U78") (pin "16") (pinfunction "2B3_16") (pintype "bidirectional"))
    )
    (net (code "204") (name "/XL.PDATA27") (class "Default")
      (node (ref "U78") (pin "17") (pinfunction "2B4_17") (pintype "bidirectional"))
    )
    (net (code "205") (name "/XL.PDATA28") (class "Default")
      (node (ref "U78") (pin "19") (pinfunction "2B5_19") (pintype "bidirectional"))
    )
    (net (code "206") (name "/XL.PDATA29") (class "Default")
      (node (ref "U78") (pin "20") (pinfunction "2B6_20") (pintype "bidirectional"))
    )
    (net (code "207") (name "/XL.PDATA30") (class "Default")
      (node (ref "U78") (pin "22") (pinfunction "2B7_22") (pintype "bidirectional"))
    )
    (net (code "208") (name "/XL.PDATA31") (class "Default")
      (node (ref "TP42") (pin "1") (pinfunction "1_1") (pintype "passive"))
      (node (ref "U78") (pin "23") (pinfunction "2B8_23") (pintype "bidirectional"))
    )
    (net (code "210") (name "/XL.PERCLK") (class "Default")
      (node (ref "C169") (pin "2") (pinfunction "2_2") (pintype "passive"))
      (node (ref "R463") (pin "2") (pinfunction "2_2") (pintype "passive"))
      (node (ref "R470") (pin "2") (pinfunction "2_2") (pintype "passive"))
      (node (ref "R65") (pin "1") (pinfunction "1_1") (pintype "passive"))
      (node (ref "R66") (pin "2") (pinfunction "2_2") (pintype "passive"))
      (node (ref "TP41") (pin "1") (pinfunction "1_1") (pintype "passive"))
    )
    (net (code "211") (name "/XL.POEn") (class "Default")
      (node (ref "U80") (pin "14") (pinfunction "1B10_14") (pintype "bidirectional"))
    )
    (net (code "212") (name "/XL.PRDY") (class "Default")
      (node (ref "R230") (pin "1") (pinfunction "1_1") (pintype "passive"))
      (node (ref "U86") (pin "1") (pinfunction "A_1") (pintype "passive"))
    )
    (net (code "213") (name "/XL.PWRn") (class "Default")
      (node (ref "U80") (pin "15") (pinfunction "2B1_15") (pintype "bidirectional"))
    )
    (net (code "216") (name "1V5") (class "Default")
      (node (ref "R476") (pin "2") (pinfunction "2_2") (pintype "passive"))
      (node (ref "U75") (pin "1") (pinfunction "VCCA_1") (pintype "power_in"))
      (node (ref "U75") (pin "5") (pinfunction "DIR_5") (pintype "input"))
    )
    (net (code "217") (name "2V5") (class "Default")
      (node (ref "C53") (pin "2") (pinfunction "2_2") (pintype "passive"))
      (node (ref "C735") (pin "2") (pinfunction "2_2") (pintype "passive"))
      (node (ref "C736") (pin "2") (pinfunction "2_2") (pintype "passive"))
      (node (ref "C739") (pin "2") (pinfunction "2_2") (pintype "passive"))
      (node (ref "C740") (pin "2") (pinfunction "2_2") (pintype "passive"))
      (node (ref "C745") (pin "2") (pinfunction "2_2") (pintype "passive"))
      (node (ref "C746") (pin "2") (pinfunction "2_2") (pintype "passive"))
      (node (ref "C749") (pin "2") (pinfunction "2_2") (pintype "passive"))
      (node (ref "C750") (pin "2") (pinfunction "2_2") (pintype "passive"))
      (node (ref "R65") (pin "2") (pinfunction "2_2") (pintype "passive"))
      (node (ref "U73") (pin "6") (pinfunction "VCCB_6") (pintype "power_in"))
      (node (ref "U74") (pin "5") (pinfunction "VCC_5") (pintype "power_in"))
      (node (ref "U76") (pin "22") (pinfunction "VCCB_22") (pintype "power_in"))
      (node (ref "U76") (pin "7") (pinfunction "VCCB_7") (pintype "power_in"))
      (node (ref "U78") (pin "18") (pinfunction "VCCB_18") (pintype "power_in"))
      (node (ref "U78") (pin "7") (pinfunction "VCCB_7") (pintype "power_in"))
      (node (ref "U80") (pin "22") (pinfunction "VCCB_22") (pintype "power_in"))
      (node (ref "U80") (pin "7") (pinfunction "VCCB_7") (pintype "power_in"))
      (node (ref "U81") (pin "18") (pinfunction "VCCB_18") (pintype "power_in"))
      (node (ref "U81") (pin "7") (pinfunction "VCCB_7") (pintype "power_in"))
    )
    (net (code "218") (name "3V3") (class "Default")
      (node (ref "C489") (pin "2") (pinfunction "2_2") (pintype "passive"))
      (node (ref "C490") (pin "2") (pinfunction "2_2") (pintype "passive"))
      (node (ref "C733") (pin "2") (pinfunction "2_2") (pintype "passive"))
      (node (ref "C734") (pin "2") (pinfunction "2_2") (pintype "passive"))
      (node (ref "C737") (pin "2") (pinfunction "2_2") (pintype "passive"))
      (node (ref "C738") (pin "2") (pinfunction "2_2") (pintype "passive"))
      (node (ref "C742") (pin "2") (pinfunction "2_2") (pintype "passive"))
      (node (ref "C743") (pin "2") (pinfunction "2_2") (pintype "passive"))
      (node (ref "C747") (pin "2") (pinfunction "2_2") (pintype "passive"))
      (node (ref "C748") (pin "2") (pinfunction "2_2") (pintype "passive"))
      (node (ref "R230") (pin "2") (pinfunction "2_2") (pintype "passive"))
      (node (ref "R269") (pin "2") (pinfunction "2_2") (pintype "passive"))
      (node (ref "R468") (pin "2") (pinfunction "2_2") (pintype "passive"))
      (node (ref "U52") (pin "5") (pinfunction "VCC_5") (pintype "passive"))
      (node (ref "U53") (pin "5") (pinfunction "VCC_5") (pintype "passive"))
      (node (ref "U73") (pin "1") (pinfunction "VCCA_1") (pintype "power_in"))
      (node (ref "U73") (pin "5") (pinfunction "DIR_5") (pintype "input"))
      (node (ref "U75") (pin "6") (pinfunction "VCCB_6") (pintype "power_in"))
      (node (ref "U76") (pin "1") (pinfunction "1DIR_1") (pintype "input"))
      (node (ref "U76") (pin "28") (pinfunction "2DIR_28") (pintype "input"))
      (node (ref "U76") (pin "35") (pinfunction "VCCA_35") (pintype "power_in"))
      (node (ref "U76") (pin "50") (pinfunction "VCCA_50") (pintype "power_in"))
      (node (ref "U78") (pin "31") (pinfunction "VCCA_31") (pintype "power_in"))
      (node (ref "U78") (pin "42") (pinfunction "VCCA_42") (pintype "power_in"))
      (node (ref "U80") (pin "1") (pinfunction "1DIR_1") (pintype "input"))
      (node (ref "U80") (pin "28") (pinfunction "2DIR_28") (pintype "input"))
      (node (ref "U80") (pin "35") (pinfunction "VCCA_35") (pintype "power_in"))
      (node (ref "U80") (pin "50") (pinfunction "VCCA_50") (pintype "power_in"))
      (node (ref "U81") (pin "31") (pinfunction "VCCA_31") (pintype "power_in"))
      (node (ref "U81") (pin "42") (pinfunction "VCCA_42") (pintype "power_in"))
      (node (ref "U86") (pin "5") (pinfunction "VCC_5") (pintype "passive"))
    )
    (net (code "219") (name "3V3AUX") (class "Default")
      (node (ref "C732") (pin "2") (pinfunction "2_2") (pintype "passive"))
      (node (ref "C741") (pin "2") (pinfunction "2_2") (pintype "passive"))
      (node (ref "C744") (pin "2") (pinfunction "2_2") (pintype "passive"))
      (node (ref "R451") (pin "2") (pinfunction "2_2") (pintype "passive"))
      (node (ref "R461") (pin "2") (pinfunction "2_2") (pintype "passive"))
      (node (ref "R49") (pin "2") (pinfunction "2_2") (pintype "passive"))
      (node (ref "R50") (pin "2") (pinfunction "2_2") (pintype "passive"))
      (node (ref "U77") (pin "20") (pinfunction "VCC_20") (pintype "power_in"))
      (node (ref "U79") (pin "20") (pinfunction "VCC_20") (pintype "power_in"))
      (node (ref "U82") (pin "20") (pinfunction "VCC_20") (pintype "power_in"))
    )
    (net (code "220") (name "GND") (class "Default")
      (node (ref "C169") (pin "1") (pinfunction "1_1") (pintype "passive"))
      (node (ref "C489") (pin "1") (pinfunction "1_1") (pintype "passive"))
      (node (ref "C490") (pin "1") (pinfunction "1_1") (pintype "passive"))
      (node (ref "C53") (pin "1") (pinfunction "1_1") (pintype "passive"))
      (node (ref "C730") (pin "1") (pinfunction "1_1") (pintype "passive"))
      (node (ref "C731") (pin "1") (pinfunction "1_1") (pintype "passive"))
      (node (ref "C732") (pin "1") (pinfunction "1_1") (pintype "passive"))
      (node (ref "C733") (pin "1") (pinfunction "1_1") (pintype "passive"))
      (node (ref "C734") (pin "1") (pinfunction "1_1") (pintype "passive"))
      (node (ref "C735") (pin "1") (pinfunction "1_1") (pintype "passive"))
      (node (ref "C736") (pin "1") (pinfunction "1_1") (pintype "passive"))
      (node (ref "C737") (pin "1") (pinfunction "1_1") (pintype "passive"))
      (node (ref "C738") (pin "1") (pinfunction "1_1") (pintype "passive"))
      (node (ref "C739") (pin "1") (pinfunction "1_1") (pintype "passive"))
      (node (ref "C740") (pin "1") (pinfunction "1_1") (pintype "passive"))
      (node (ref "C741") (pin "1") (pinfunction "1_1") (pintype "passive"))
      (node (ref "C742") (pin "1") (pinfunction "1_1") (pintype "passive"))
      (node (ref "C743") (pin "1") (pinfunction "1_1") (pintype "passive"))
      (node (ref "C744") (pin "1") (pinfunction "1_1") (pintype "passive"))
      (node (ref "C745") (pin "1") (pinfunction "1_1") (pintype "passive"))
      (node (ref "C746") (pin "1") (pinfunction "1_1") (pintype "passive"))
      (node (ref "C747") (pin "1") (pinfunction "1_1") (pintype "passive"))
      (node (ref "C748") (pin "1") (pinfunction "1_1") (pintype "passive"))
      (node (ref "C749") (pin "1") (pinfunction "1_1") (pintype "passive"))
      (node (ref "C750") (pin "1") (pinfunction "1_1") (pintype "passive"))
      (node (ref "P17") (pin "16") (pinfunction "B16_16") (pintype "output"))
      (node (ref "R252") (pin "1") (pinfunction "1_1") (pintype "passive"))
      (node (ref "R66") (pin "1") (pinfunction "1_1") (pintype "passive"))
      (node (ref "U52") (pin "2") (pinfunction "GND_2") (pintype "passive"))
      (node (ref "U53") (pin "2") (pinfunction "GND_2") (pintype "passive"))
      (node (ref "U73") (pin "2") (pinfunction "GND_2") (pintype "input"))
      (node (ref "U74") (pin "3") (pinfunction "GND_3") (pintype "power_in"))
      (node (ref "U75") (pin "2") (pinfunction "GND_2") (pintype "input"))
      (node (ref "U76") (pin "11") (pinfunction "GND_11") (pintype "power_in"))
      (node (ref "U76") (pin "18") (pinfunction "GND_18") (pintype "power_in"))
      (node (ref "U76") (pin "25") (pinfunction "GND_25") (pintype "power_in"))
      (node (ref "U76") (pin "29") (pinfunction "2OEn_29") (pintype "input"))
      (node (ref "U76") (pin "32") (pinfunction "GND_32") (pintype "power_in"))
      (node (ref "U76") (pin "39") (pinfunction "GND_39") (pintype "power_in"))
      (node (ref "U76") (pin "4") (pinfunction "GND_4") (pintype "power_in"))
      (node (ref "U76") (pin "46") (pinfunction "GND_46") (pintype "power_in"))
      (node (ref "U76") (pin "53") (pinfunction "GND_53") (pintype "power_in"))
      (node (ref "U76") (pin "56") (pinfunction "1OEn_56") (pintype "input"))
      (node (ref "U77") (pin "10") (pinfunction "GND_10") (pintype "power_in"))
      (node (ref "U78") (pin "10") (pinfunction "GND_10") (pintype "power_in"))
      (node (ref "U78") (pin "15") (pinfunction "GND_15") (pintype "power_in"))
      (node (ref "U78") (pin "21") (pinfunction "GND_21") (pintype "power_in"))
      (node (ref "U78") (pin "25") (pinfunction "2OEn_25") (pintype "input"))
      (node (ref "U78") (pin "28") (pinfunction "GND_28") (pintype "power_in"))
      (node (ref "U78") (pin "34") (pinfunction "GND_34") (pintype "power_in"))
      (node (ref "U78") (pin "39") (pinfunction "GND_39") (pintype "power_in"))
      (node (ref "U78") (pin "4") (pinfunction "GND_4") (pintype "power_in"))
      (node (ref "U78") (pin "45") (pinfunction "GND_45") (pintype "power_in"))
      (node (ref "U78") (pin "48") (pinfunction "1OEn_48") (pintype "input"))
      (node (ref "U79") (pin "10") (pinfunction "GND_10") (pintype "power_in"))
      (node (ref "U80") (pin "11") (pinfunction "GND_11") (pintype "power_in"))
      (node (ref "U80") (pin "18") (pinfunction "GND_18") (pintype "power_in"))
      (node (ref "U80") (pin "25") (pinfunction "GND_25") (pintype "power_in"))
      (node (ref "U80") (pin "29") (pinfunction "2OEn_29") (pintype "input"))
      (node (ref "U80") (pin "30") (pinfunction "2A10_30") (pintype "bidirectional"))
      (node (ref "U80") (pin "31") (pinfunction "2A9_31") (pintype "bidirectional"))
      (node (ref "U80") (pin "32") (pinfunction "GND_32") (pintype "power_in"))
      (node (ref "U80") (pin "33") (pinfunction "2A8_33") (pintype "bidirectional"))
      (node (ref "U80") (pin "34") (pinfunction "2A7_34") (pintype "bidirectional"))
      (node (ref "U80") (pin "36") (pinfunction "2A6_36") (pintype "bidirectional"))
      (node (ref "U80") (pin "39") (pinfunction "GND_39") (pintype "power_in"))
      (node (ref "U80") (pin "4") (pinfunction "GND_4") (pintype "power_in"))
      (node (ref "U80") (pin "46") (pinfunction "GND_46") (pintype "power_in"))
      (node (ref "U80") (pin "53") (pinfunction "GND_53") (pintype "power_in"))
      (node (ref "U80") (pin "56") (pinfunction "1OEn_56") (pintype "input"))
      (node (ref "U81") (pin "10") (pinfunction "GND_10") (pintype "power_in"))
      (node (ref "U81") (pin "15") (pinfunction "GND_15") (pintype "power_in"))
      (node (ref "U81") (pin "21") (pinfunction "GND_21") (pintype "power_in"))
      (node (ref "U81") (pin "25") (pinfunction "2OEn_25") (pintype "input"))
      (node (ref "U81") (pin "28") (pinfunction "GND_28") (pintype "power_in"))
      (node (ref "U81") (pin "34") (pinfunction "GND_34") (pintype "power_in"))
      (node (ref "U81") (pin "39") (pinfunction "GND_39") (pintype "power_in"))
      (node (ref "U81") (pin "4") (pinfunction "GND_4") (pintype "power_in"))
      (node (ref "U81") (pin "45") (pinfunction "GND_45") (pintype "power_in"))
      (node (ref "U81") (pin "48") (pinfunction "1OEn_48") (pintype "input"))
      (node (ref "U82") (pin "10") (pinfunction "GND_10") (pintype "power_in"))
      (node (ref "U86") (pin "3") (pinfunction "GND_3") (pintype "passive"))
    )
    (net (code "221") (name "Net-(P17-A1)") (class "Default")
      (node (ref "P17") (pin "1") (pinfunction "A1_1") (pintype "output"))
      (node (ref "R471") (pin "2") (pinfunction "2_2") (pintype "passive"))
    )
    (net (code "222") (name "Net-(P17-A3)") (class "Default")
      (node (ref "P17") (pin "3") (pinfunction "A3_3") (pintype "output"))
      (node (ref "R472") (pin "2") (pinfunction "2_2") (pintype "passive"))
    )
    (net (code "223") (name "Net-(P17-A7)") (class "Default")
      (node (ref "P17") (pin "7") (pinfunction "A7_7") (pintype "output"))
      (node (ref "R474") (pin "2") (pinfunction "2_2") (pintype "passive"))
    )
    (net (code "224") (name "Net-(P17-A9)") (class "Default")
      (node (ref "P17") (pin "9") (pinfunction "A9_9") (pintype "output"))
      (node (ref "R475") (pin "2") (pinfunction "2_2") (pintype "passive"))
    )
    (net (code "225") (name "Net-(P17-B4)") (class "Default")
      (node (ref "P17") (pin "4") (pinfunction "B4_4") (pintype "output"))
      (node (ref "R473") (pin "1") (pinfunction "1_1") (pintype "passive"))
    )
    (net (code "226") (name "Net-(U73-B)") (class "Default")
      (node (ref "R463") (pin "1") (pinfunction "1_1") (pintype "passive"))
      (node (ref "U73") (pin "4") (pinfunction "B_4") (pintype "bidirectional"))
    )
    (net (code "227") (name "Net-(U74-Y)") (class "Default")
      (node (ref "R470") (pin "1") (pinfunction "1_1") (pintype "passive"))
      (node (ref "U74") (pin "4") (pinfunction "Y_4") (pintype "output"))
    )
    (net (code "228") (name "Net-(U78-1DIR)") (class "Default")
      (node (ref "R487") (pin "2") (pinfunction "2_2") (pintype "passive"))
      (node (ref "U78") (pin "1") (pinfunction "1DIR_1") (pintype "input"))
      (node (ref "U78") (pin "24") (pinfunction "2DIR_24") (pintype "input"))
    )
    (net (code "229") (name "Net-(U81-1DIR)") (class "Default")
      (node (ref "R490") (pin "2") (pinfunction "2_2") (pintype "passive"))
      (node (ref "U81") (pin "1") (pinfunction "1DIR_1") (pintype "input"))
      (node (ref "U81") (pin "24") (pinfunction "2DIR_24") (pintype "input"))
    )
    (net (code "230") (name "VCC_JTAG") (class "Default")
      (node (ref "C730") (pin "2") (pinfunction "2_2") (pintype "passive"))
      (node (ref "C731") (pin "2") (pinfunction "2_2") (pintype "passive"))
      (node (ref "P17") (pin "6") (pinfunction "B6_6") (pintype "output"))
      (node (ref "R468") (pin "1") (pinfunction "1_1") (pintype "passive"))
    )
    (net (code "231") (name "unconnected-(P17-A5-Pad5)") (class "Default")
      (node (ref "P17") (pin "5") (pinfunction "A5_5") (pintype "output+no_connect"))
    )
    (net (code "232") (name "unconnected-(P17-A13-Pad13)") (class "Default")
      (node (ref "P17") (pin "13") (pinfunction "A13_13") (pintype "output+no_connect"))
    )
    (net (code "233") (name "unconnected-(P17-A15-Pad15)") (class "Default")
      (node (ref "P17") (pin "15") (pinfunction "A15_15") (pintype "output+no_connect"))
    )
    (net (code "234") (name "unconnected-(P17-B2-Pad2)") (class "Default")
      (node (ref "P17") (pin "2") (pinfunction "B2_2") (pintype "output+no_connect"))
    )
    (net (code "235") (name "unconnected-(P17-B8-Pad8)") (class "Default")
      (node (ref "P17") (pin "8") (pinfunction "B8_8") (pintype "output+no_connect"))
    )
    (net (code "236") (name "unconnected-(P17-B10-Pad10)") (class "Default")
      (node (ref "P17") (pin "10") (pinfunction "B10_10") (pintype "output+no_connect"))
    )
    (net (code "237") (name "unconnected-(P17-B12-Pad12)") (class "Default")
      (node (ref "P17") (pin "12") (pinfunction "B12_12") (pintype "output+no_connect"))
    )
    (net (code "238") (name "unconnected-(P17-B14-Pad14)") (class "Default")
      (node (ref "P17") (pin "14") (pinfunction "B14_14") (pintype "output+no_connect"))
    )
    (net (code "239") (name "unconnected-(U74-NC-Pad1)") (class "Default")
      (node (ref "U74") (pin "1") (pinfunction "NC_1") (pintype "passive+no_connect"))
    )
    (net (code "240") (name "unconnected-(U80-2B6-Pad21)") (class "Default")
      (node (ref "U80") (pin "21") (pinfunction "2B6_21") (pintype "bidirectional+no_connect"))
    )
    (net (code "241") (name "unconnected-(U80-2B7-Pad23)") (class "Default")
      (node (ref "U80") (pin "23") (pinfunction "2B7_23") (pintype "bidirectional+no_connect"))
    )
    (net (code "242") (name "unconnected-(U80-2B8-Pad24)") (class "Default")
      (node (ref "U80") (pin "24") (pinfunction "2B8_24") (pintype "bidirectional+no_connect"))
    )
    (net (code "243") (name "unconnected-(U80-2B9-Pad26)") (class "Default")
      (node (ref "U80") (pin "26") (pinfunction "2B9_26") (pintype "bidirectional+no_connect"))
    )
    (net (code "244") (name "unconnected-(U80-2B10-Pad27)") (class "Default")
      (node (ref "U80") (pin "27") (pinfunction "2B10_27") (pintype "bidirectional+no_connect"))
    )
  )
)
